# Transceiver.net
KiCad netlist of a schematic drawn in Altium Designer
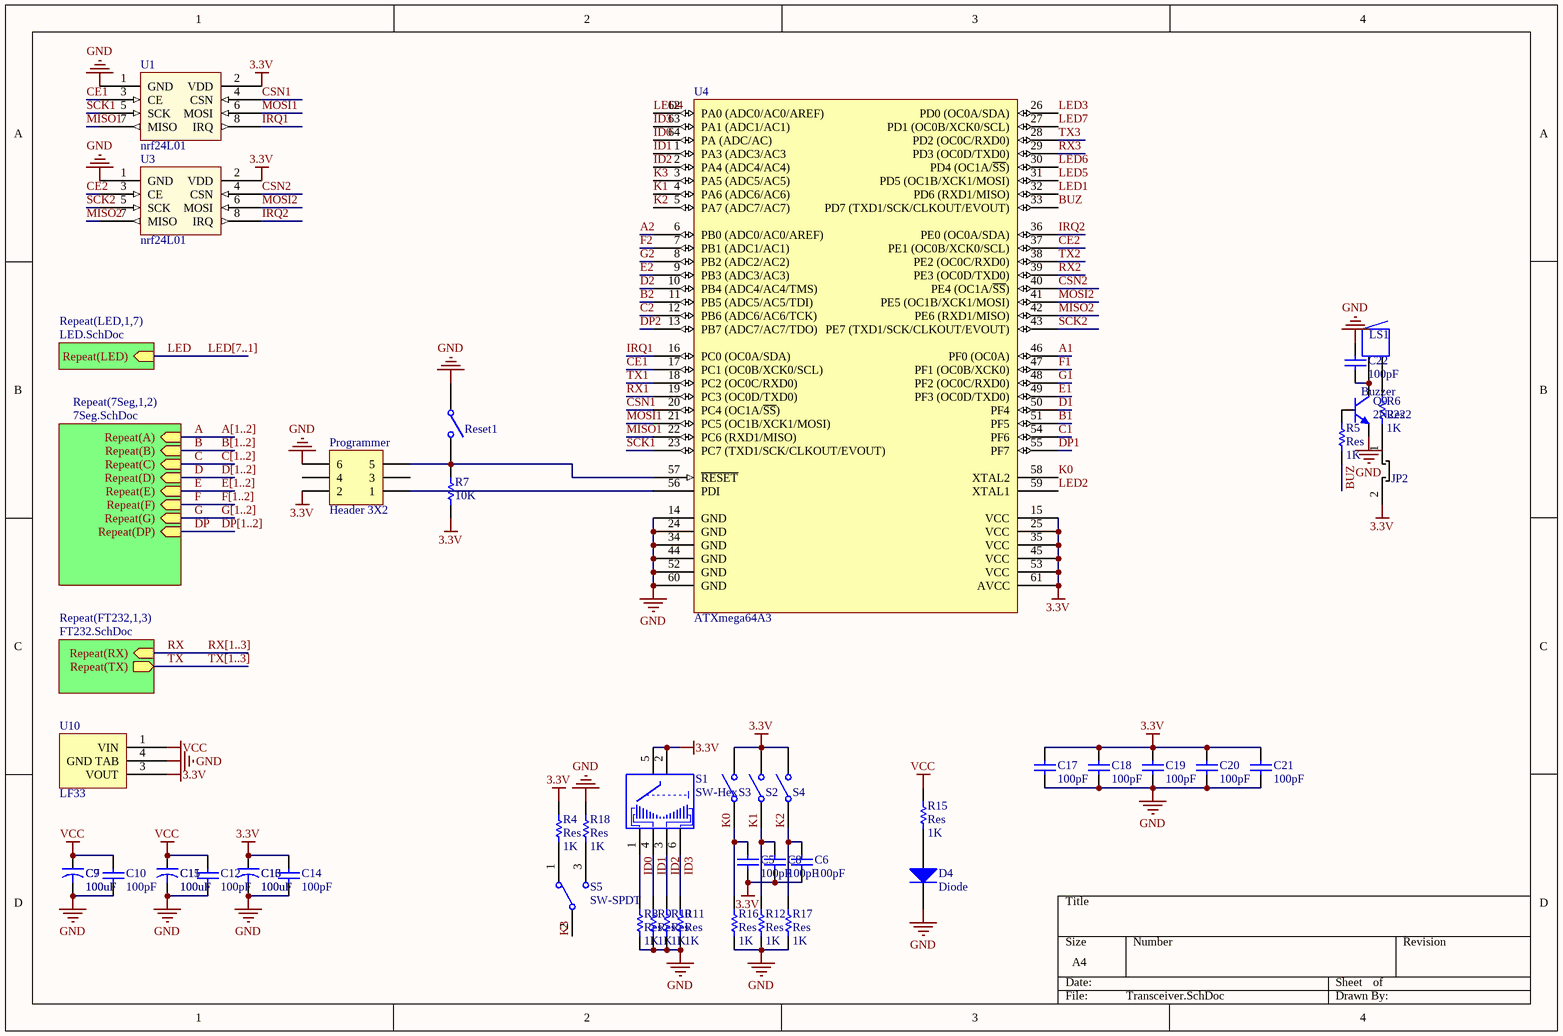
[diagram p0: Transceiver.SchDoc]

(export (version "E")
  (design (tool "Eeschema 10.0.6"))
  (components
    (comp (ref "C5")
      (value "100pF")
      (footprint "2012[0805]")
      (description "Capacitor")
      (fields (field (name "Comment") "Cap_UP") (field (name "PUBLISHER") "Altium Limited"))
      (libsource (lib "KN2CLib") (part "Cap_UP"))
    )
    (comp (ref "C6")
      (value "100pF")
      (footprint "2012[0805]")
      (description "Capacitor")
      (fields (field (name "Comment") "Cap_UP") (field (name "PUBLISHER") "Altium Limited"))
      (libsource (lib "KN2CLib") (part "Cap_UP"))
    )
    (comp (ref "C7")
      (value "100uF")
      (footprint "EL_M")
      (description "Capacitor")
      (fields (field (name "Comment") "Cap_El") (field (name "PUBLISHER") "Altium Limited"))
      (libsource (lib "KN2CLib") (part "Cap_El"))
    )
    (comp (ref "C8")
      (value "100pF")
      (footprint "2012[0805]")
      (description "Capacitor")
      (fields (field (name "Comment") "Cap_UP") (field (name "PUBLISHER") "Altium Limited"))
      (libsource (lib "KN2CLib") (part "Cap_UP"))
    )
    (comp (ref "C9")
      (value "100uF")
      (footprint "EL_M")
      (description "Capacitor")
      (fields (field (name "Comment") "Cap_El") (field (name "PUBLISHER") "Altium Limited"))
      (libsource (lib "KN2CLib") (part "Cap_El"))
    )
    (comp (ref "C10")
      (value "100pF")
      (footprint "2012[0805]")
      (description "Capacitor")
      (fields (field (name "Comment") "Cap_UP") (field (name "PUBLISHER") "Altium Limited"))
      (libsource (lib "KN2CLib") (part "Cap_UP"))
    )
    (comp (ref "C11")
      (value "100uF")
      (footprint "EL_M")
      (description "Capacitor")
      (fields (field (name "Comment") "Cap_El") (field (name "PUBLISHER") "Altium Limited"))
      (libsource (lib "KN2CLib") (part "Cap_El"))
    )
    (comp (ref "C12")
      (value "100pF")
      (footprint "2012[0805]")
      (description "Capacitor")
      (fields (field (name "Comment") "Cap_UP") (field (name "PUBLISHER") "Altium Limited"))
      (libsource (lib "KN2CLib") (part "Cap_UP"))
    )
    (comp (ref "C13")
      (value "100uF")
      (footprint "EL_M")
      (description "Capacitor")
      (fields (field (name "Comment") "Cap_El") (field (name "PUBLISHER") "Altium Limited"))
      (libsource (lib "KN2CLib") (part "Cap_El"))
    )
    (comp (ref "C14")
      (value "100pF")
      (footprint "2012[0805]")
      (description "Capacitor")
      (fields (field (name "Comment") "Cap_UP") (field (name "PUBLISHER") "Altium Limited"))
      (libsource (lib "KN2CLib") (part "Cap_UP"))
    )
    (comp (ref "C15")
      (value "100uF")
      (footprint "EL_M")
      (description "Capacitor")
      (fields (field (name "Comment") "Cap_El") (field (name "PUBLISHER") "Altium Limited"))
      (libsource (lib "KN2CLib") (part "Cap_El"))
    )
    (comp (ref "C16")
      (value "100uF")
      (footprint "EL_M")
      (description "Capacitor")
      (fields (field (name "Comment") "Cap_El") (field (name "PUBLISHER") "Altium Limited"))
      (libsource (lib "KN2CLib") (part "Cap_El"))
    )
    (comp (ref "C17")
      (value "100pF")
      (footprint "2012[0805]")
      (description "Capacitor")
      (fields (field (name "Comment") "Cap_UP") (field (name "PUBLISHER") "Altium Limited"))
      (libsource (lib "KN2CLib") (part "Cap_UP"))
    )
    (comp (ref "C18")
      (value "100pF")
      (footprint "2012[0805]")
      (description "Capacitor")
      (fields (field (name "Comment") "Cap_UP") (field (name "PUBLISHER") "Altium Limited"))
      (libsource (lib "KN2CLib") (part "Cap_UP"))
    )
    (comp (ref "C19")
      (value "100pF")
      (footprint "2012[0805]")
      (description "Capacitor")
      (fields (field (name "Comment") "Cap_UP") (field (name "PUBLISHER") "Altium Limited"))
      (libsource (lib "KN2CLib") (part "Cap_UP"))
    )
    (comp (ref "C20")
      (value "100pF")
      (footprint "2012[0805]")
      (description "Capacitor")
      (fields (field (name "Comment") "Cap_UP") (field (name "PUBLISHER") "Altium Limited"))
      (libsource (lib "KN2CLib") (part "Cap_UP"))
    )
    (comp (ref "C21")
      (value "100pF")
      (footprint "2012[0805]")
      (description "Capacitor")
      (fields (field (name "Comment") "Cap_UP") (field (name "PUBLISHER") "Altium Limited"))
      (libsource (lib "KN2CLib") (part "Cap_UP"))
    )
    (comp (ref "C22")
      (value "100pF")
      (footprint "2012[0805]")
      (description "Capacitor")
      (fields (field (name "Comment") "Cap_UP") (field (name "PUBLISHER") "Altium Limited"))
      (libsource (lib "KN2CLib") (part "Cap_UP"))
    )
    (comp (ref "D4")
      (value "Diode")
      (footprint "2012[0805]")
      (description "1 Amp General Purpose Rectifier")
      (fields (field (name "PUBLISHER") "Altium Limited"))
      (libsource (lib "KN2CLib") (part "Diode"))
    )
    (comp (ref "JP2") (value "JUMPER") (footprint "HDR1X2") (libsource (lib "KN2CLib") (part "JUMPER")))
    (comp (ref "LS1")
      (value "Buzzer")
      (footprint "BUZZER")
      (description "Magnetic Transducer Buzzer")
      (fields (field (name "PUBLISHER") "Altium Limited"))
      (libsource (lib "KN2CLib") (part "Buzzer"))
    )
    (comp (ref "Programmer")
      (value "Header 3X2")
      (footprint "HDRBOX2X3")
      (description "Header, 3-Pin, Dual row")
      (fields (field (name "PUBLISHER") "Altium Limited"))
      (libsource (lib "KN2CLib") (part "Header 3X2"))
    )
    (comp (ref "Q9")
      (value "2N2222")
      (footprint "SOT-23")
      (description "NPN Bipolar Transistor")
      (fields (field (name "PUBLISHER") "Altium Limited"))
      (libsource (lib "KN2CLib") (part "2N2222"))
    )
    (comp (ref "R4")
      (value "Res")
      (footprint "2012[0805]")
      (description "Semiconductor Resistor")
      (fields (field (name "ALTIUM_VALUE") "1K") (field (name "PUBLISHER") "Altium Limited"))
      (libsource (lib "KN2CLib") (part "Res"))
    )
    (comp (ref "R5")
      (value "Res")
      (footprint "2012[0805]")
      (description "Semiconductor Resistor")
      (fields (field (name "ALTIUM_VALUE") "1K") (field (name "PUBLISHER") "Altium Limited"))
      (libsource (lib "KN2CLib") (part "Res"))
    )
    (comp (ref "R6")
      (value "Res")
      (footprint "2012[0805]")
      (description "Semiconductor Resistor")
      (fields (field (name "ALTIUM_VALUE") "1K") (field (name "PUBLISHER") "Altium Limited"))
      (libsource (lib "KN2CLib") (part "Res"))
    )
    (comp (ref "R7")
      (value "10K")
      (footprint "2012[0805]")
      (description "Semiconductor Resistor")
      (fields (field (name "PUBLISHER") "Altium Limited"))
      (libsource (lib "KN2CLib") (part "Res"))
    )
    (comp (ref "R8")
      (value "Res")
      (footprint "2012[0805]")
      (description "Semiconductor Resistor")
      (fields (field (name "ALTIUM_VALUE") "1K") (field (name "PUBLISHER") "Altium Limited"))
      (libsource (lib "KN2CLib") (part "Res"))
    )
    (comp (ref "R9")
      (value "Res")
      (footprint "2012[0805]")
      (description "Semiconductor Resistor")
      (fields (field (name "ALTIUM_VALUE") "1K") (field (name "PUBLISHER") "Altium Limited"))
      (libsource (lib "KN2CLib") (part "Res"))
    )
    (comp (ref "R10")
      (value "Res")
      (footprint "2012[0805]")
      (description "Semiconductor Resistor")
      (fields (field (name "ALTIUM_VALUE") "1K") (field (name "PUBLISHER") "Altium Limited"))
      (libsource (lib "KN2CLib") (part "Res"))
    )
    (comp (ref "R11")
      (value "Res")
      (footprint "2012[0805]")
      (description "Semiconductor Resistor")
      (fields (field (name "ALTIUM_VALUE") "1K") (field (name "PUBLISHER") "Altium Limited"))
      (libsource (lib "KN2CLib") (part "Res"))
    )
    (comp (ref "R12")
      (value "Res")
      (footprint "2012[0805]")
      (description "Semiconductor Resistor")
      (fields (field (name "ALTIUM_VALUE") "1K") (field (name "PUBLISHER") "Altium Limited"))
      (libsource (lib "KN2CLib") (part "Res"))
    )
    (comp (ref "R15")
      (value "Res")
      (footprint "2012[0805]")
      (description "Semiconductor Resistor")
      (fields (field (name "ALTIUM_VALUE") "1K") (field (name "PUBLISHER") "Altium Limited"))
      (libsource (lib "KN2CLib") (part "Res"))
    )
    (comp (ref "R16")
      (value "Res")
      (footprint "2012[0805]")
      (description "Semiconductor Resistor")
      (fields (field (name "ALTIUM_VALUE") "1K") (field (name "PUBLISHER") "Altium Limited"))
      (libsource (lib "KN2CLib") (part "Res"))
    )
    (comp (ref "R17")
      (value "Res")
      (footprint "2012[0805]")
      (description "Semiconductor Resistor")
      (fields (field (name "ALTIUM_VALUE") "1K") (field (name "PUBLISHER") "Altium Limited"))
      (libsource (lib "KN2CLib") (part "Res"))
    )
    (comp (ref "R18")
      (value "Res")
      (footprint "2012[0805]")
      (description "Semiconductor Resistor")
      (fields (field (name "ALTIUM_VALUE") "1K") (field (name "PUBLISHER") "Altium Limited"))
      (libsource (lib "KN2CLib") (part "Res"))
    )
    (comp (ref "Reset1")
      (value "SW-SPST")
      (footprint "PUSH-BUT")
      (description "Single-Pole, Single-Throw Switch")
      (fields (field (name "PUBLISHER") "Altium Limited"))
      (libsource (lib "KN2CLib") (part "SW-SPST"))
    )
    (comp (ref "S1")
      (value "SW-Hex")
      (footprint "SW-HEX")
      (fields (field (name "PUBLISHER") "Altium Limited"))
      (libsource (lib "KN2CLib") (part "SW-Hex"))
    )
    (comp (ref "S2")
      (value "SW-SPST")
      (footprint "PUSH-BUT-SMD")
      (description "Single-Pole, Single-Throw Switch")
      (fields (field (name "PUBLISHER") "Altium Limited"))
      (libsource (lib "KN2CLib") (part "SW-SPST"))
    )
    (comp (ref "S3")
      (value "SW-SPST")
      (footprint "PUSH-BUT")
      (description "Single-Pole, Single-Throw Switch")
      (fields (field (name "PUBLISHER") "Altium Limited"))
      (libsource (lib "KN2CLib") (part "SW-SPST"))
    )
    (comp (ref "S4")
      (value "SW-SPST")
      (footprint "PUSH-BUT")
      (description "Single-Pole, Single-Throw Switch")
      (fields (field (name "PUBLISHER") "Altium Limited"))
      (libsource (lib "KN2CLib") (part "SW-SPST"))
    )
    (comp (ref "S5")
      (value "SW-SPDT")
      (footprint "SW-SPDT")
      (description "SPDT Subminiature Toggle Switch, Right Angle Mounting, Vertical Actuation")
      (fields (field (name "PUBLISHER") "Altium Limited"))
      (libsource (lib "KN2CLib") (part "SW-SPDT"))
    )
    (comp (ref "U1")
      (value "nrf24L01")
      (footprint "NRF24L01+PA+LNA")
      (libsource (lib "KN2CLib") (part "nrf24L01"))
    )
    (comp (ref "U3")
      (value "nrf24L01")
      (footprint "NRF24L01+PA+LNA")
      (libsource (lib "KN2CLib") (part "nrf24L01"))
    )
    (comp (ref "U4")
      (value "ATXmega64A3")
      (footprint "64A_N")
      (libsource (lib "KN2CLib") (part "ATXmega64A3"))
    )
    (comp (ref "U10") (value "LF33") (footprint "D-PACK") (libsource (lib "KN2CLib") (part "7805")))
  )
  (nets
    (net (code "2") (name "/A1") (class "Default")
      (node (ref "U4") (pin "46") (pinfunction "PF0_(OC0A)_46") (pintype "bidirectional"))
    )
    (net (code "3") (name "/A2") (class "Default")
      (node (ref "U4") (pin "6") (pinfunction "PB0_(ADC0/AC0/AREF)_6") (pintype "bidirectional"))
    )
    (net (code "6") (name "/B1") (class "Default")
      (node (ref "U4") (pin "51") (pinfunction "PF5_51") (pintype "bidirectional"))
    )
    (net (code "7") (name "/B2") (class "Default")
      (node (ref "U4") (pin "11") (pinfunction "PB5_(ADC5/AC5/TDI)_11") (pintype "bidirectional"))
    )
    (net (code "8") (name "/BUZ") (class "Default")
      (node (ref "R5") (pin "2") (pinfunction "2_2") (pintype "passive"))
      (node (ref "U4") (pin "33") (pinfunction "PD7_(TXD1/SCK/CLKOUT/EVOUT)_33") (pintype "bidirectional"))
    )
    (net (code "11") (name "/C1") (class "Default")
      (node (ref "U4") (pin "54") (pinfunction "PF6_54") (pintype "bidirectional"))
    )
    (net (code "12") (name "/C2") (class "Default")
      (node (ref "U4") (pin "12") (pinfunction "PB6_(ADC6/AC6/TCK)_12") (pintype "bidirectional"))
    )
    (net (code "13") (name "/CE1") (class "Default")
      (node (ref "U1") (pin "3") (pinfunction "CE_3") (pintype "input"))
      (node (ref "U4") (pin "17") (pinfunction "PC1_(OC0B/XCK0/SCL)_17") (pintype "bidirectional"))
    )
    (net (code "14") (name "/CE2") (class "Default")
      (node (ref "U3") (pin "3") (pinfunction "CE_3") (pintype "input"))
      (node (ref "U4") (pin "37") (pinfunction "PE1_(OC0B/XCK0/SCL)_37") (pintype "bidirectional"))
    )
    (net (code "15") (name "/CSN1") (class "Default")
      (node (ref "U1") (pin "4") (pinfunction "CSN_4") (pintype "input"))
      (node (ref "U4") (pin "20") (pinfunction "PC4_(OC1A/~{SS})_20") (pintype "bidirectional"))
    )
    (net (code "16") (name "/CSN2") (class "Default")
      (node (ref "U3") (pin "4") (pinfunction "CSN_4") (pintype "input"))
      (node (ref "U4") (pin "40") (pinfunction "PE4_(OC1A/~{SS})_40") (pintype "bidirectional"))
    )
    (net (code "19") (name "/D1") (class "Default")
      (node (ref "U4") (pin "50") (pinfunction "PF4_50") (pintype "bidirectional"))
    )
    (net (code "20") (name "/D2") (class "Default")
      (node (ref "U4") (pin "10") (pinfunction "PB4_(ADC4/AC4/TMS)_10") (pintype "bidirectional"))
    )
    (net (code "22") (name "/DP1") (class "Default")
      (node (ref "U4") (pin "55") (pinfunction "PF7_55") (pintype "bidirectional"))
    )
    (net (code "23") (name "/DP2") (class "Default")
      (node (ref "U4") (pin "13") (pinfunction "PB7_(ADC7/AC7/TDO)_13") (pintype "bidirectional"))
    )
    (net (code "27") (name "/E1") (class "Default")
      (node (ref "U4") (pin "49") (pinfunction "PF3_(OC0D/TXD0)_49") (pintype "bidirectional"))
    )
    (net (code "28") (name "/E2") (class "Default")
      (node (ref "U4") (pin "9") (pinfunction "PB3_(ADC3/AC3)_9") (pintype "bidirectional"))
    )
    (net (code "31") (name "/F1") (class "Default")
      (node (ref "U4") (pin "47") (pinfunction "PF1_(OC0B/XCK0)_47") (pintype "bidirectional"))
    )
    (net (code "32") (name "/F2") (class "Default")
      (node (ref "U4") (pin "7") (pinfunction "PB1_(ADC1/AC1)_7") (pintype "bidirectional"))
    )
    (net (code "35") (name "/G1") (class "Default")
      (node (ref "U4") (pin "48") (pinfunction "PF2_(OC0C/RXD0)_48") (pintype "bidirectional"))
    )
    (net (code "36") (name "/G2") (class "Default")
      (node (ref "U4") (pin "8") (pinfunction "PB2_(ADC2/AC2)_8") (pintype "bidirectional"))
    )
    (net (code "38") (name "/ID0") (class "Default")
      (node (ref "R8") (pin "2") (pinfunction "2_2") (pintype "passive"))
      (node (ref "S1") (pin "1") (pinfunction "1_1") (pintype "passive"))
      (node (ref "U4") (pin "64") (pinfunction "PA_(ADC/AC)_64") (pintype "bidirectional"))
    )
    (net (code "39") (name "/ID1") (class "Default")
      (node (ref "R9") (pin "2") (pinfunction "2_2") (pintype "passive"))
      (node (ref "S1") (pin "4") (pinfunction "4_4") (pintype "passive"))
      (node (ref "U4") (pin "1") (pinfunction "PA3_(ADC3/AC3_1") (pintype "bidirectional"))
    )
    (net (code "40") (name "/ID2") (class "Default")
      (node (ref "R10") (pin "2") (pinfunction "2_2") (pintype "passive"))
      (node (ref "S1") (pin "3") (pinfunction "3_3") (pintype "passive"))
      (node (ref "U4") (pin "2") (pinfunction "PA4_(ADC4/AC4)_2") (pintype "bidirectional"))
    )
    (net (code "41") (name "/ID3") (class "Default")
      (node (ref "R11") (pin "2") (pinfunction "2_2") (pintype "passive"))
      (node (ref "S1") (pin "6") (pinfunction "6_6") (pintype "passive"))
      (node (ref "U4") (pin "63") (pinfunction "PA1_(ADC1/AC1)_63") (pintype "bidirectional"))
    )
    (net (code "42") (name "/IRQ1") (class "Default")
      (node (ref "U1") (pin "8") (pinfunction "IRQ_8") (pintype "output"))
      (node (ref "U4") (pin "16") (pinfunction "PC0_(OC0A/SDA)_16") (pintype "bidirectional"))
    )
    (net (code "43") (name "/IRQ2") (class "Default")
      (node (ref "U3") (pin "8") (pinfunction "IRQ_8") (pintype "output"))
      (node (ref "U4") (pin "36") (pinfunction "PE0_(OC0A/SDA)_36") (pintype "bidirectional"))
    )
    (net (code "44") (name "/K0") (class "Default")
      (node (ref "C5") (pin "1") (pinfunction "1_1") (pintype "passive"))
      (node (ref "R16") (pin "2") (pinfunction "2_2") (pintype "passive"))
      (node (ref "S3") (pin "1") (pinfunction "COMMON_1") (pintype "passive"))
      (node (ref "U4") (pin "58") (pinfunction "XTAL2_58") (pintype "passive"))
    )
    (net (code "45") (name "/K1") (class "Default")
      (node (ref "C8") (pin "1") (pinfunction "1_1") (pintype "passive"))
      (node (ref "R12") (pin "2") (pinfunction "2_2") (pintype "passive"))
      (node (ref "S2") (pin "1") (pinfunction "COMMON_1") (pintype "passive"))
      (node (ref "U4") (pin "4") (pinfunction "PA6_(ADC6/AC6)_4") (pintype "bidirectional"))
    )
    (net (code "46") (name "/K2") (class "Default")
      (node (ref "C6") (pin "1") (pinfunction "1_1") (pintype "passive"))
      (node (ref "R17") (pin "2") (pinfunction "2_2") (pintype "passive"))
      (node (ref "S4") (pin "1") (pinfunction "COMMON_1") (pintype "passive"))
      (node (ref "U4") (pin "5") (pinfunction "PA7_(ADC7/AC7)_5") (pintype "bidirectional"))
    )
    (net (code "47") (name "/K3") (class "Default")
      (node (ref "S5") (pin "2") (pinfunction "2_2") (pintype "passive"))
      (node (ref "U4") (pin "3") (pinfunction "PA5_(ADC5/AC5)_3") (pintype "bidirectional"))
    )
    (net (code "49") (name "/LED1") (class "Default")
      (node (ref "U4") (pin "32") (pinfunction "PD6_(RXD1/MISO)_32") (pintype "bidirectional"))
    )
    (net (code "50") (name "/LED2") (class "Default")
      (node (ref "U4") (pin "59") (pinfunction "XTAL1_59") (pintype "passive"))
    )
    (net (code "51") (name "/LED3") (class "Default")
      (node (ref "U4") (pin "26") (pinfunction "PD0_(OC0A/SDA)_26") (pintype "bidirectional"))
    )
    (net (code "52") (name "/LED4") (class "Default")
      (node (ref "U4") (pin "62") (pinfunction "PA0_(ADC0/AC0/AREF)_62") (pintype "bidirectional"))
    )
    (net (code "53") (name "/LED5") (class "Default")
      (node (ref "U4") (pin "31") (pinfunction "PD5_(OC1B/XCK1/MOSI)_31") (pintype "bidirectional"))
    )
    (net (code "54") (name "/LED6") (class "Default")
      (node (ref "U4") (pin "30") (pinfunction "PD4_(OC1A/~{SS})_30") (pintype "bidirectional"))
    )
    (net (code "55") (name "/LED7") (class "Default")
      (node (ref "U4") (pin "27") (pinfunction "PD1_(OC0B/XCK0/SCL)_27") (pintype "bidirectional"))
    )
    (net (code "57") (name "/MISO1") (class "Default")
      (node (ref "U1") (pin "7") (pinfunction "MISO_7") (pintype "output"))
      (node (ref "U4") (pin "22") (pinfunction "PC6_(RXD1/MISO)_22") (pintype "bidirectional"))
    )
    (net (code "58") (name "/MISO2") (class "Default")
      (node (ref "U3") (pin "7") (pinfunction "MISO_7") (pintype "output"))
      (node (ref "U4") (pin "42") (pinfunction "PE6_(RXD1/MISO)_42") (pintype "bidirectional"))
    )
    (net (code "59") (name "/MOSI1") (class "Default")
      (node (ref "U1") (pin "6") (pinfunction "MOSI_6") (pintype "input"))
      (node (ref "U4") (pin "21") (pinfunction "PC5_(OC1B/XCK1/MOSI)_21") (pintype "bidirectional"))
    )
    (net (code "60") (name "/MOSI2") (class "Default")
      (node (ref "U3") (pin "6") (pinfunction "MOSI_6") (pintype "input"))
      (node (ref "U4") (pin "41") (pinfunction "PE5_(OC1B/XCK1/MOSI)_41") (pintype "bidirectional"))
    )
    (net (code "62") (name "/RX1") (class "Default")
      (node (ref "U4") (pin "19") (pinfunction "PC3_(OC0D/TXD0)_19") (pintype "bidirectional"))
    )
    (net (code "63") (name "/RX2") (class "Default")
      (node (ref "U4") (pin "39") (pinfunction "PE3_(OC0D/TXD0)_39") (pintype "bidirectional"))
    )
    (net (code "64") (name "/RX3") (class "Default")
      (node (ref "U4") (pin "29") (pinfunction "PD3_(OC0D/TXD0)_29") (pintype "bidirectional"))
    )
    (net (code "66") (name "/SCK1") (class "Default")
      (node (ref "U1") (pin "5") (pinfunction "SCK_5") (pintype "input"))
      (node (ref "U4") (pin "23") (pinfunction "PC7_(TXD1/SCK/CLKOUT/EVOUT)_23") (pintype "bidirectional"))
    )
    (net (code "67") (name "/SCK2") (class "Default")
      (node (ref "U3") (pin "5") (pinfunction "SCK_5") (pintype "input"))
      (node (ref "U4") (pin "43") (pinfunction "PE7_(TXD1/SCK/CLKOUT/EVOUT)_43") (pintype "bidirectional"))
    )
    (net (code "69") (name "/TX1") (class "Default")
      (node (ref "U4") (pin "18") (pinfunction "PC2_(OC0C/RXD0)_18") (pintype "bidirectional"))
    )
    (net (code "70") (name "/TX2") (class "Default")
      (node (ref "U4") (pin "38") (pinfunction "PE2_(OC0C/RXD0)_38") (pintype "bidirectional"))
    )
    (net (code "71") (name "/TX3") (class "Default")
      (node (ref "U4") (pin "28") (pinfunction "PD2_(OC0C/RXD0)_28") (pintype "bidirectional"))
    )
    (net (code "73") (name "3.3V") (class "Default")
      (node (ref "C13") (pin "1") (pinfunction "1_1") (pintype "passive"))
      (node (ref "C14") (pin "2") (pinfunction "2_2") (pintype "passive"))
      (node (ref "C16") (pin "1") (pinfunction "1_1") (pintype "passive"))
      (node (ref "C17") (pin "2") (pinfunction "2_2") (pintype "passive"))
      (node (ref "C18") (pin "2") (pinfunction "2_2") (pintype "passive"))
      (node (ref "C19") (pin "2") (pinfunction "2_2") (pintype "passive"))
      (node (ref "C20") (pin "2") (pinfunction "2_2") (pintype "passive"))
      (node (ref "C21") (pin "2") (pinfunction "2_2") (pintype "passive"))
      (node (ref "C5") (pin "2") (pinfunction "2_2") (pintype "passive"))
      (node (ref "C6") (pin "2") (pinfunction "2_2") (pintype "passive"))
      (node (ref "C8") (pin "2") (pinfunction "2_2") (pintype "passive"))
      (node (ref "JP2") (pin "2") (pinfunction "2_2") (pintype "passive"))
      (node (ref "Programmer") (pin "2") (pinfunction "2_2") (pintype "passive"))
      (node (ref "R4") (pin "2") (pinfunction "2_2") (pintype "passive"))
      (node (ref "R7") (pin "1") (pinfunction "1_1") (pintype "passive"))
      (node (ref "S1") (pin "2") (pinfunction "2_2") (pintype "passive"))
      (node (ref "S1") (pin "5") (pinfunction "5_5") (pintype "passive"))
      (node (ref "S2") (pin "2") (pinfunction "NO_2") (pintype "passive"))
      (node (ref "S3") (pin "2") (pinfunction "NO_2") (pintype "passive"))
      (node (ref "S4") (pin "2") (pinfunction "NO_2") (pintype "passive"))
      (node (ref "U1") (pin "2") (pinfunction "VDD_2") (pintype "power_in"))
      (node (ref "U10") (pin "3") (pinfunction "VOUT_3") (pintype "passive"))
      (node (ref "U3") (pin "2") (pinfunction "VDD_2") (pintype "power_in"))
      (node (ref "U4") (pin "15") (pinfunction "VCC_15") (pintype "power_in"))
      (node (ref "U4") (pin "25") (pinfunction "VCC_25") (pintype "power_in"))
      (node (ref "U4") (pin "35") (pinfunction "VCC_35") (pintype "power_in"))
      (node (ref "U4") (pin "45") (pinfunction "VCC_45") (pintype "power_in"))
      (node (ref "U4") (pin "53") (pinfunction "VCC_53") (pintype "power_in"))
      (node (ref "U4") (pin "61") (pinfunction "AVCC_61") (pintype "power_in"))
    )
    (net (code "74") (name "GND") (class "Default")
      (node (ref "C10") (pin "1") (pinfunction "1_1") (pintype "passive"))
      (node (ref "C11") (pin "2") (pinfunction "2_2") (pintype "passive"))
      (node (ref "C12") (pin "1") (pinfunction "1_1") (pintype "passive"))
      (node (ref "C13") (pin "2") (pinfunction "2_2") (pintype "passive"))
      (node (ref "C14") (pin "1") (pinfunction "1_1") (pintype "passive"))
      (node (ref "C15") (pin "2") (pinfunction "2_2") (pintype "passive"))
      (node (ref "C16") (pin "2") (pinfunction "2_2") (pintype "passive"))
      (node (ref "C17") (pin "1") (pinfunction "1_1") (pintype "passive"))
      (node (ref "C18") (pin "1") (pinfunction "1_1") (pintype "passive"))
      (node (ref "C19") (pin "1") (pinfunction "1_1") (pintype "passive"))
      (node (ref "C20") (pin "1") (pinfunction "1_1") (pintype "passive"))
      (node (ref "C21") (pin "1") (pinfunction "1_1") (pintype "passive"))
      (node (ref "C22") (pin "2") (pinfunction "2_2") (pintype "passive"))
      (node (ref "C7") (pin "2") (pinfunction "2_2") (pintype "passive"))
      (node (ref "C9") (pin "2") (pinfunction "2_2") (pintype "passive"))
      (node (ref "D4") (pin "2") (pinfunction "K_2") (pintype "passive"))
      (node (ref "Programmer") (pin "6") (pinfunction "6_6") (pintype "passive"))
      (node (ref "Q9") (pin "3") (pinfunction "E_3") (pintype "passive"))
      (node (ref "R10") (pin "1") (pinfunction "1_1") (pintype "passive"))
      (node (ref "R11") (pin "1") (pinfunction "1_1") (pintype "passive"))
      (node (ref "R12") (pin "1") (pinfunction "1_1") (pintype "passive"))
      (node (ref "R16") (pin "1") (pinfunction "1_1") (pintype "passive"))
      (node (ref "R17") (pin "1") (pinfunction "1_1") (pintype "passive"))
      (node (ref "R18") (pin "2") (pinfunction "2_2") (pintype "passive"))
      (node (ref "R8") (pin "1") (pinfunction "1_1") (pintype "passive"))
      (node (ref "R9") (pin "1") (pinfunction "1_1") (pintype "passive"))
      (node (ref "Reset1") (pin "1") (pinfunction "COMMON_1") (pintype "passive"))
      (node (ref "U1") (pin "1") (pinfunction "GND_1") (pintype "power_in"))
      (node (ref "U10") (pin "4") (pinfunction "GND_TAB_4") (pintype "passive"))
      (node (ref "U3") (pin "1") (pinfunction "GND_1") (pintype "power_in"))
      (node (ref "U4") (pin "14") (pinfunction "GND_14") (pintype "power_in"))
      (node (ref "U4") (pin "24") (pinfunction "GND_24") (pintype "power_in"))
      (node (ref "U4") (pin "34") (pinfunction "GND_34") (pintype "power_in"))
      (node (ref "U4") (pin "44") (pinfunction "GND_44") (pintype "power_in"))
      (node (ref "U4") (pin "52") (pinfunction "GND_52") (pintype "power_in"))
      (node (ref "U4") (pin "60") (pinfunction "GND_60") (pintype "power_in"))
    )
    (net (code "75") (name "Net-(D4-A)") (class "Default")
      (node (ref "D4") (pin "1") (pinfunction "A_1") (pintype "passive"))
      (node (ref "R15") (pin "2") (pinfunction "2_2") (pintype "passive"))
    )
    (net (code "76") (name "Net-(JP2-Pad1)") (class "Default")
      (node (ref "JP2") (pin "1") (pinfunction "1_1") (pintype "passive"))
      (node (ref "R6") (pin "2") (pinfunction "2_2") (pintype "passive"))
    )
    (net (code "77") (name "Net-(LS1-Pad2)") (class "Default")
      (node (ref "LS1") (pin "2") (pinfunction "2_2") (pintype "passive"))
      (node (ref "R6") (pin "1") (pinfunction "1_1") (pintype "passive"))
    )
    (net (code "78") (name "Net-(Q9-B)") (class "Default")
      (node (ref "Q9") (pin "2") (pinfunction "B_2") (pintype "passive"))
      (node (ref "R5") (pin "1") (pinfunction "1_1") (pintype "passive"))
    )
    (net (code "79") (name "Net-(Q9-C)") (class "Default")
      (node (ref "C22") (pin "1") (pinfunction "1_1") (pintype "passive"))
      (node (ref "LS1") (pin "1") (pinfunction "1_1") (pintype "passive"))
      (node (ref "Q9") (pin "1") (pinfunction "C_1") (pintype "passive"))
    )
    (net (code "80") (name "Net-(Reset1-NO)") (class "Default")
      (node (ref "Programmer") (pin "5") (pinfunction "5_5") (pintype "passive"))
      (node (ref "R7") (pin "2") (pinfunction "2_2") (pintype "passive"))
      (node (ref "Reset1") (pin "2") (pinfunction "NO_2") (pintype "passive"))
      (node (ref "U4") (pin "57") (pinfunction "~{RESET}_57") (pintype "input"))
    )
    (net (code "81") (name "Net-(S5-1)") (class "Default")
      (node (ref "R18") (pin "1") (pinfunction "1_1") (pintype "passive"))
      (node (ref "S5") (pin "3") (pinfunction "1_3") (pintype "passive"))
    )
    (net (code "82") (name "Net-(S5-3)") (class "Default")
      (node (ref "R4") (pin "1") (pinfunction "1_1") (pintype "passive"))
      (node (ref "S5") (pin "1") (pinfunction "3_1") (pintype "passive"))
    )
    (net (code "83") (name "Net-(U4-PDI)") (class "Default")
      (node (ref "Programmer") (pin "1") (pinfunction "1_1") (pintype "passive"))
      (node (ref "U4") (pin "56") (pinfunction "PDI_56") (pintype "passive"))
    )
    (net (code "84") (name "VCC") (class "Default")
      (node (ref "C10") (pin "2") (pinfunction "2_2") (pintype "passive"))
      (node (ref "C11") (pin "1") (pinfunction "1_1") (pintype "passive"))
      (node (ref "C12") (pin "2") (pinfunction "2_2") (pintype "passive"))
      (node (ref "C15") (pin "1") (pinfunction "1_1") (pintype "passive"))
      (node (ref "C7") (pin "1") (pinfunction "1_1") (pintype "passive"))
      (node (ref "C9") (pin "1") (pinfunction "1_1") (pintype "passive"))
      (node (ref "R15") (pin "1") (pinfunction "1_1") (pintype "passive"))
      (node (ref "U10") (pin "1") (pinfunction "VIN_1") (pintype "passive"))
    )
    (net (code "85") (name "unconnected-(Programmer-Pad3)") (class "Default")
      (node (ref "Programmer") (pin "3") (pinfunction "3_3") (pintype "passive"))
    )
    (net (code "86") (name "unconnected-(Programmer-Pad4)") (class "Default")
      (node (ref "Programmer") (pin "4") (pinfunction "4_4") (pintype "passive"))
    )
  )
)
